# Dash.net
KiCad netlist of a schematic drawn in Altium Designer
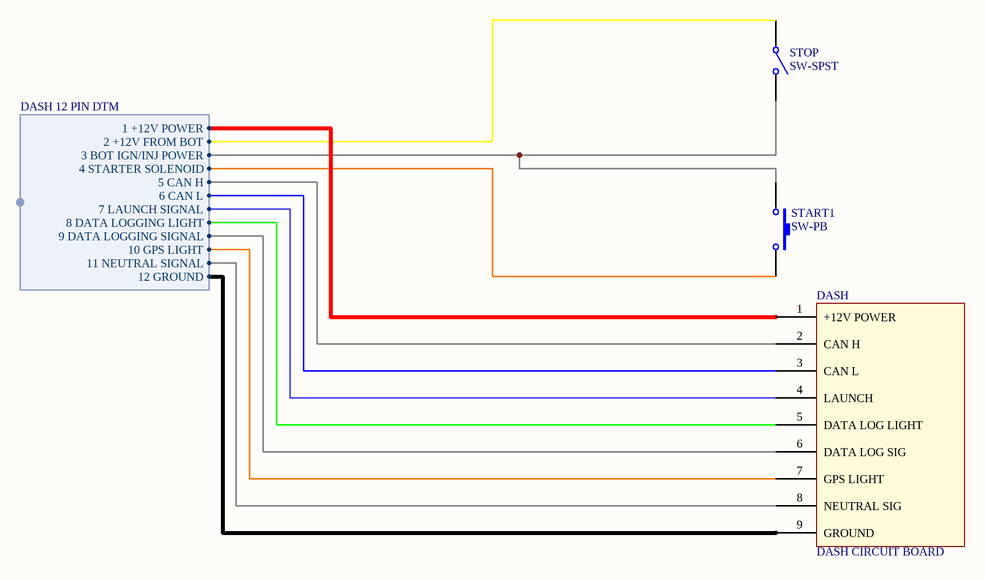
[diagram p0: Dash.SchDoc]

(export (version "E")
  (design (tool "Eeschema 10.0.6"))
  (components
    (comp (ref "DASH")
      (value "DASH CIRCUIT BOARD")
      (libsource (lib "Loom Components") (part "DASH CIRCUIT BOARD"))
    )
    (comp (ref "START1")
      (value "SW-PB")
      (footprint "SPST-2")
      (description "Switch")
      (fields (field (name "PUBLISHER") "Altium Limited"))
      (libsource (lib "Miscellaneous Devices") (part "SW-PB"))
    )
    (comp (ref "STOP")
      (value "SW-SPST")
      (footprint "SPST-2")
      (description "Single-Pole, Single-Throw Switch")
      (fields (field (name "PUBLISHER") "Altium Limited"))
      (libsource (lib "Miscellaneous Devices") (part "SW-SPST"))
    )
  )
  (nets
    (net (code "1") (name "/1 +12V POWER") (class "Default")
      (node (ref "DASH") (pin "1") (pinfunction "+12V_POWER_1") (pintype "passive"))
    )
    (net (code "2") (name "/2 +12V FROM BOT") (class "Default")
      (node (ref "STOP") (pin "1") (pinfunction "COMMON_1") (pintype "passive"))
    )
    (net (code "3") (name "/3 BOT IGN{slash}INJ POWER") (class "Default")
      (node (ref "START1") (pin "1") (pinfunction "1_1") (pintype "passive"))
      (node (ref "STOP") (pin "2") (pinfunction "NO_2") (pintype "passive"))
    )
    (net (code "4") (name "/4 STARTER SOLENOID") (class "Default")
      (node (ref "START1") (pin "2") (pinfunction "2_2") (pintype "passive"))
    )
    (net (code "5") (name "/5 CAN H") (class "Default")
      (node (ref "DASH") (pin "2") (pinfunction "CAN_H_2") (pintype "passive"))
    )
    (net (code "6") (name "/6 CAN L") (class "Default")
      (node (ref "DASH") (pin "3") (pinfunction "CAN_L_3") (pintype "passive"))
    )
    (net (code "7") (name "/7 LAUNCH SIGNAL") (class "Default")
      (node (ref "DASH") (pin "4") (pinfunction "LAUNCH_4") (pintype "passive"))
    )
    (net (code "8") (name "/8 DATA LOGGING LIGHT") (class "Default")
      (node (ref "DASH") (pin "5") (pinfunction "DATA_LOG_LIGHT_5") (pintype "passive"))
    )
    (net (code "9") (name "/9 DATA LOGGING SIGNAL") (class "Default")
      (node (ref "DASH") (pin "6") (pinfunction "DATA_LOG_SIG_6") (pintype "passive"))
    )
    (net (code "10") (name "/10 GPS LIGHT") (class "Default")
      (node (ref "DASH") (pin "7") (pinfunction "GPS_LIGHT_7") (pintype "passive"))
    )
    (net (code "11") (name "/11 NEUTRAL SIGNAL") (class "Default")
      (node (ref "DASH") (pin "8") (pinfunction "NEUTRAL_SIG_8") (pintype "passive"))
    )
    (net (code "12") (name "/12 GROUND") (class "Default")
      (node (ref "DASH") (pin "9") (pinfunction "GROUND_9") (pintype "passive"))
    )
  )
)
